# ECG_PWR_MGMT.net
KiCad netlist of a schematic drawn in Altium Designer
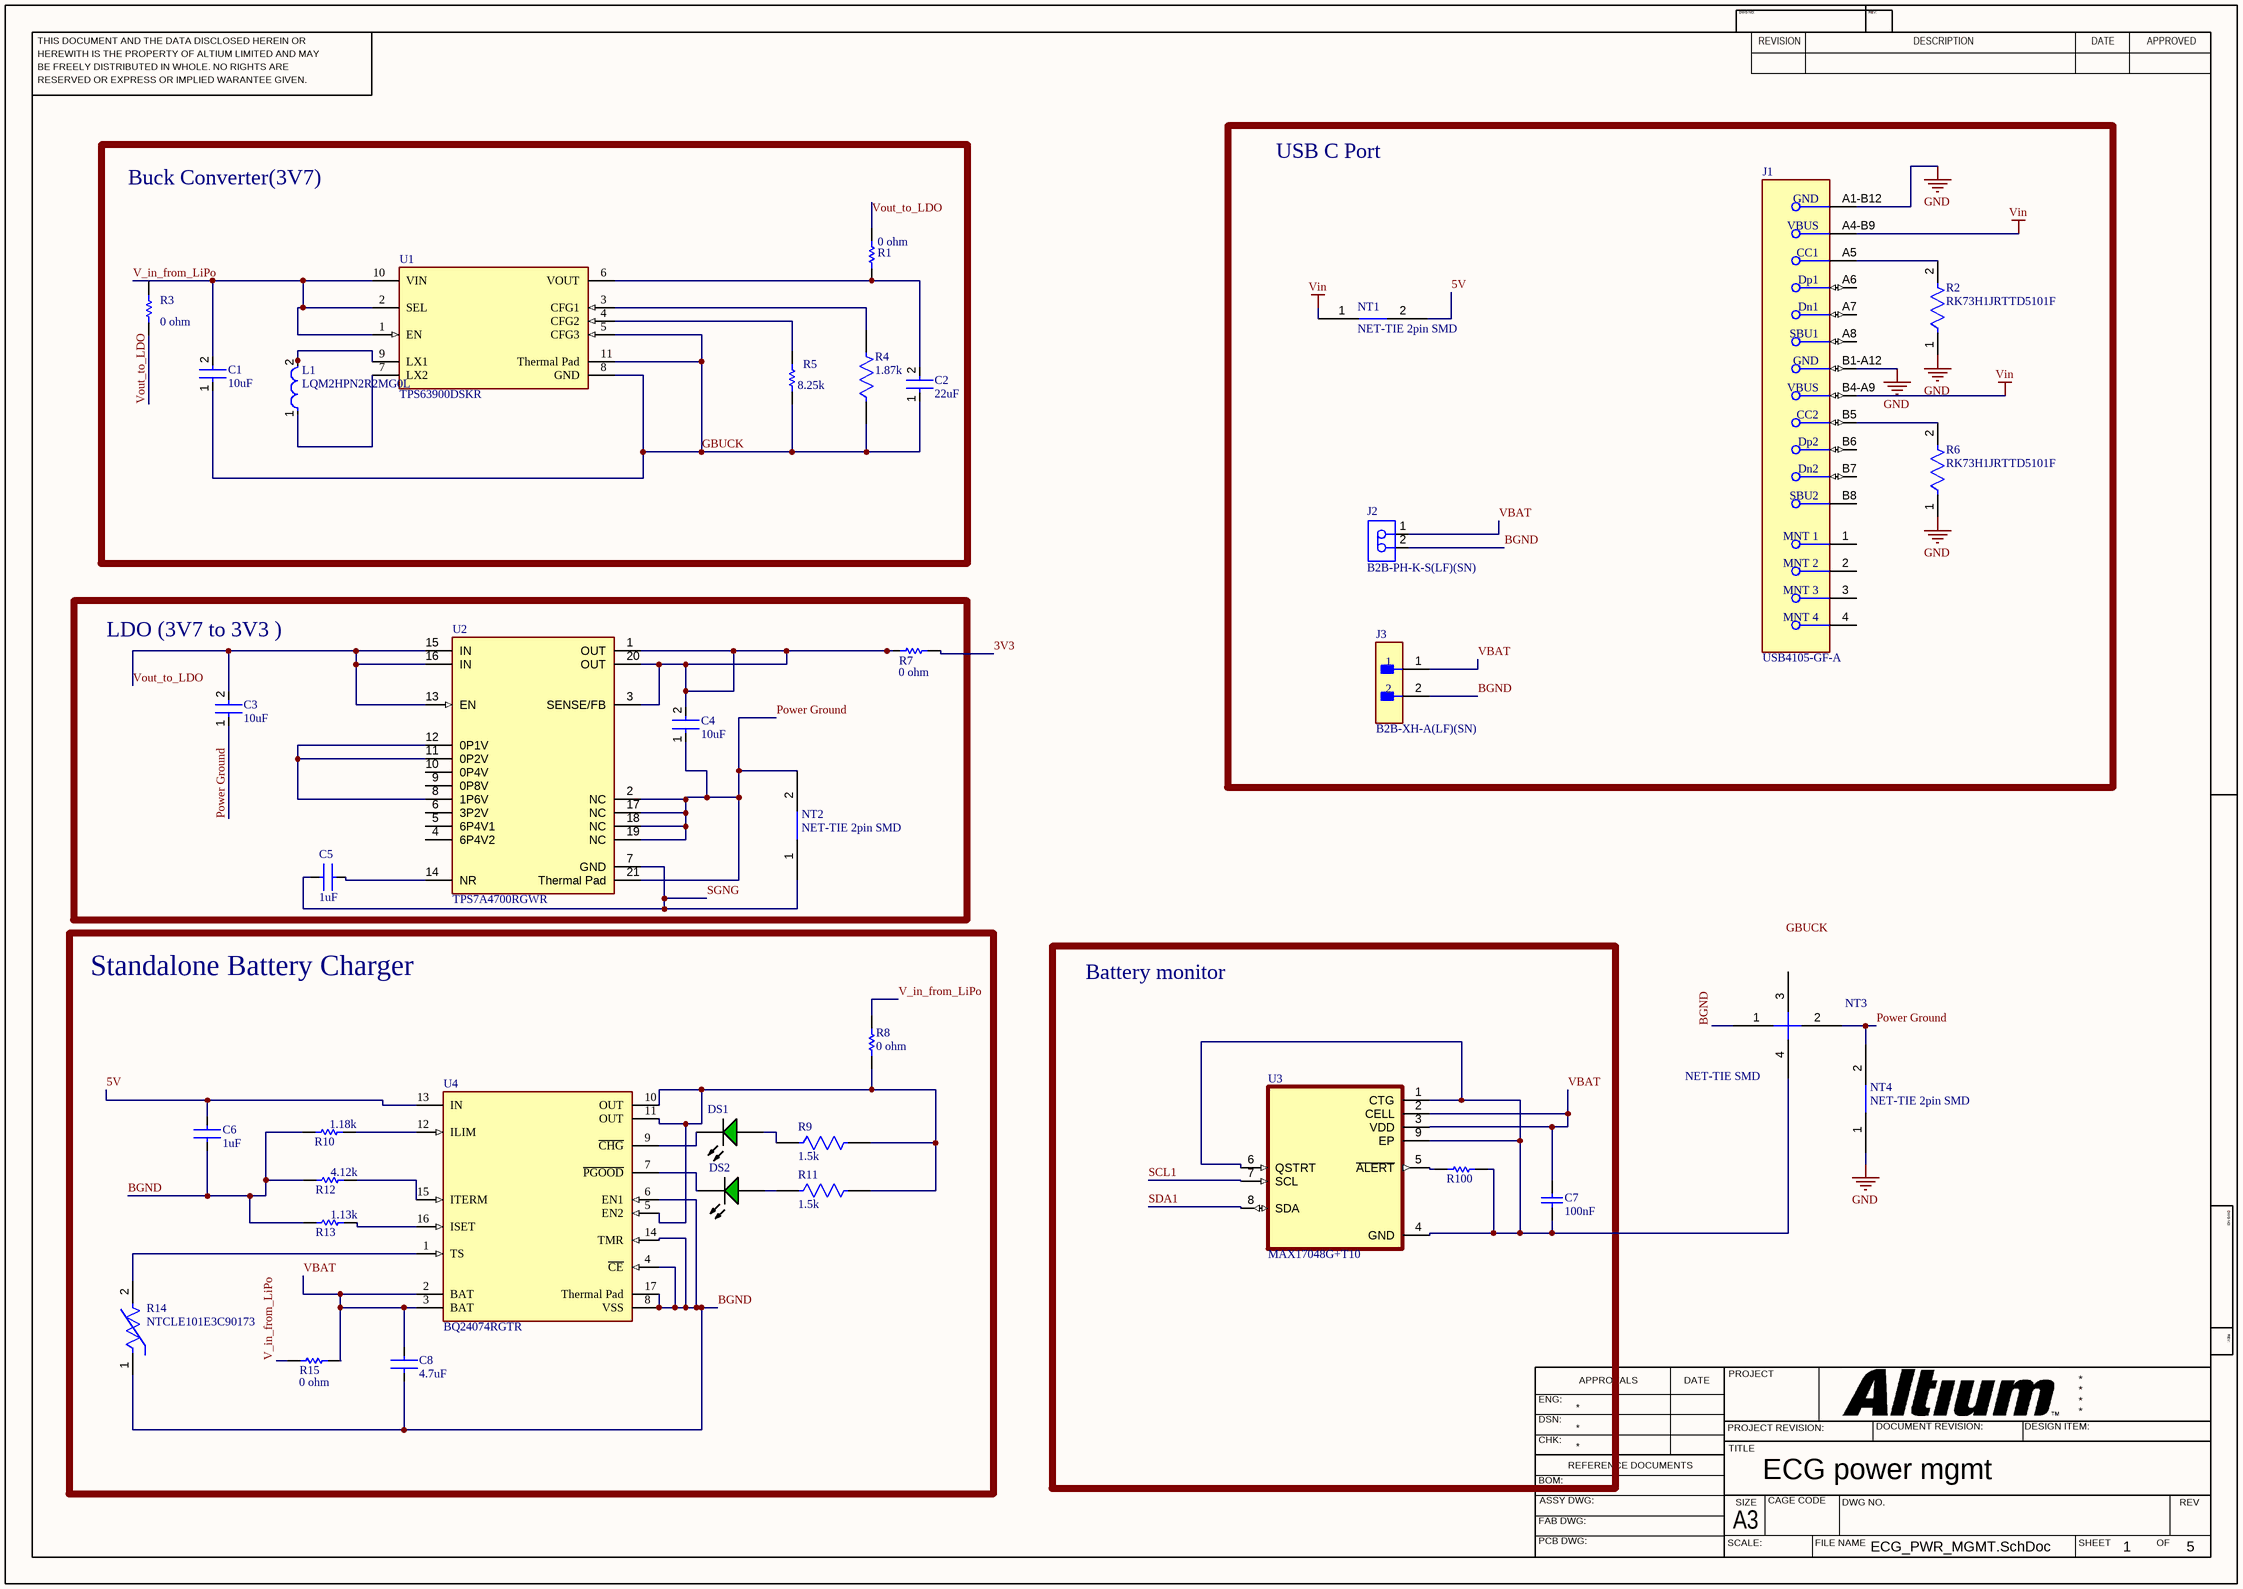
[diagram p0: ECG_PWR_MGMT.SchDoc]

(export (version "E")
  (design (tool "Eeschema 10.0.6"))
  (components
    (comp (ref "C1")
      (value "10uF")
      (footprint "CAP-0805-IPC_B")
      (description "50V 10uF X5R 卤10% 0805 Multilayer Ceramic Capacitors MLCC - SMD/SMT ROHS")
      (fields
        (field (name "MANUFACTURER") "Samsung Electro-Mechanics")
        (field (name "MANUFACTURER PART NUMBER") "CL21A106KBYQNNE")
      )
      (libsource (lib "ecg_device_components") (part "10uF CAP 0805 10V"))
    )
    (comp (ref "C2")
      (value "22uF")
      (footprint "CAP-0805-IPC_B")
      (description "10V 22uF X5R 卤10% 0805 Multilayer Ceramic Capacitors MLCC - SMD/SMT ROHS")
      (fields
        (field (name "MANUFACTURER") "Samsung Electro-Mechanics")
        (field (name "MANUFACTURER PART NUMBER") "CL21A226KPCLRNC")
      )
      (libsource (lib "ecg_device_components") (part "22uF CAP-0805-IPC-B_2"))
    )
    (comp (ref "C3")
      (value "10uF")
      (footprint "CAP-0805-IPC_B")
      (description "50V 10uF X5R 卤10% 0805 Multilayer Ceramic Capacitors MLCC - SMD/SMT ROHS")
      (fields
        (field (name "MANUFACTURER") "Samsung Electro-Mechanics")
        (field (name "MANUFACTURER PART NUMBER") "CL21A106KBYQNNE")
      )
      (libsource (lib "ecg_device_components") (part "10uF CAP 0805 10V"))
    )
    (comp (ref "C4")
      (value "10uF")
      (footprint "CAP-0805-IPC_B")
      (description "50V 10uF X5R 卤10% 0805 Multilayer Ceramic Capacitors MLCC - SMD/SMT ROHS")
      (fields
        (field (name "MANUFACTURER") "Samsung Electro-Mechanics")
        (field (name "MANUFACTURER PART NUMBER") "CL21A106KBYQNNE")
      )
      (libsource (lib "ecg_device_components") (part "10uF CAP 0805 10V"))
    )
    (comp (ref "C5")
      (value "1uF")
      (footprint "CAP-0805-IPC_B")
      (libsource (lib "ecg_device_components") (part "1uF CAP-0805-IPC-B_1"))
    )
    (comp (ref "C6")
      (value "1uF")
      (footprint "CAP-0805-IPC_B")
      (libsource (lib "ecg_device_components") (part "1uF CAP-0805-IPC-B_1"))
    )
    (comp (ref "C7")
      (value "100nF")
      (footprint "CAP-0603-IPC_B")
      (fields
        (field (name "MANUFACTURER") "AVX Interconnect / Elco")
        (field (name "PART NUMBER") "0603ZC103MAT2A")
      )
      (libsource (lib "ecg_device_components") (part "CAP-0603-IPC-B"))
    )
    (comp (ref "C8")
      (value "4.7uF")
      (footprint "CAP-0805-IPC_B")
      (libsource (lib "ecg_device_components") (part "4.7uF CAP-0805-IPC-B_1"))
    )
    (comp (ref "DS1")
      (value "LTL-1CHG")
      (footprint "LTST-LTL-1CHG-2")
      (description "LED Uni-Color Green, 100 mW, 30 mA, -55 to 100 degC, 2-Pin THD, RoHS, Bulk")
      (fields (field (name "POWER") "100mW") (field (name "MANUFACTURER") "Lite-On"))
      (libsource (lib "Dissanayakadmdp 23") (part "LED-GREEN-AK-2"))
    )
    (comp (ref "DS2")
      (value "LTL-1CHG")
      (footprint "LTST-LTL-1CHG-2")
      (description "LED Uni-Color Green, 100 mW, 30 mA, -55 to 100 degC, 2-Pin THD, RoHS, Bulk")
      (fields (field (name "POWER") "100mW") (field (name "MANUFACTURER") "Lite-On"))
      (libsource (lib "Dissanayakadmdp 23") (part "LED-GREEN-AK-2"))
    )
    (comp (ref "J1")
      (value "USB4105-GF-A")
      (footprint "FP-USB4105-GF-A-MFG")
      (description "CONN RCPT USB2.0 TYPEC 5A")
      (fields
        (field (name "MANUFACTURER") "GCT")
        (field (name "OCTOPART") "https://octopart.com/usb4105-gf-a-gct-106627878")
      )
      (libsource (lib "Altium Content Vault") (part "e7c17a616881a82b79941196b4bec10"))
    )
    (comp (ref "J2")
      (value "B2B-PH-K-S(LF)(SN)")
      (footprint "JST-B2B-PH-K-S_V")
      (fields (field (name "MANUFACTURER") "JST"))
      (libsource (lib "Altium Content Vault") (part "CN-2P-F-QF2"))
    )
    (comp (ref "J3")
      (value "B2B-XH-A(LF)(SN)")
      (footprint "FP-B2B-XH-A_LF_SN-MFG")
      (description "CONN HEADER VERT 2POS 2.5MM")
      (libsource (lib "Altium Content Vault") (part "3bc925449376181038e59eaffc5286c"))
    )
    (comp (ref "L1")
      (value "LQM2HPN2R2MG0L")
      (footprint "FP-LQM2HPN_G0-IPC_C")
      (description "Multilayer Type Inductor for Power Lines, 1008 (2520), 2.2μH, 20%, 0.1Ω, 1.3A")
      (fields (field (name "TOLERANCE") "20%"))
      (libsource (lib "Altium Content Vault") (part "725321dda6339637d4d059423bc1c3c"))
    )
    (comp (ref "NT1")
      (value "NET-TIE 2pin SMD")
      (footprint "NET TIE SMD 2 pin")
      (libsource (lib "ecg_device_components") (part "NET-TIE 2pin SMD"))
    )
    (comp (ref "NT2")
      (value "NET-TIE 2pin SMD")
      (footprint "NET TIE SMD 2 pin")
      (libsource (lib "ecg_device_components") (part "NET-TIE 2pin SMD"))
    )
    (comp (ref "NT3")
      (value "NET-TIE SMD")
      (footprint "NET TIE SMD")
      (libsource (lib "ecg_device_components") (part "NET-TIE SMD"))
    )
    (comp (ref "NT4")
      (value "NET-TIE 2pin SMD")
      (footprint "NET TIE SMD 2 pin")
      (libsource (lib "ecg_device_components") (part "NET-TIE 2pin SMD"))
    )
    (comp (ref "R1")
      (value "0 ohm")
      (footprint "RES-0603-IPC_B")
      (fields (field (name "TOLERANCE") "0.5%"))
      (libsource (lib "ecg_device_components") (part "RES-0603-IPC-B"))
    )
    (comp (ref "R2")
      (value "RK73H1JRTTD5101F")
      (footprint "FP-RK73H1J-IPC_C")
      (description "5.1kΩ ±1% 0.1W Chip Resistor 0603 Flat Chip (Anti-Sulfuration) AEC-Q200 Qualified")
      (fields (field (name "TOLERANCE") "1%"))
      (libsource (lib "Altium Content Vault") (part "1029c3af85768c4190bb7ad29bc67b5"))
    )
    (comp (ref "R3")
      (value "0 ohm")
      (footprint "RES-0603-IPC_B")
      (fields (field (name "TOLERANCE") "0.5%"))
      (libsource (lib "ecg_device_components") (part "RES-0603-IPC-B"))
    )
    (comp (ref "R4")
      (value "1.87k")
      (footprint "RES 0805 Medium")
      (description "200mW Thick Film Resistors ±50ppm/℃ ±0.1% 1.87kΩ 0805 Chip Resistor - Surface Mount ROHS")
      (fields
        (field (name "MANUFACTURER") "Panasonic")
        (field (name "MANUFACTURER PART NUMBER") "ERJPB6B1871V")
      )
      (libsource (lib "ecg_device_components") (part "1.87k RES-0805-IPC_B_1"))
    )
    (comp (ref "R5")
      (value "8.25k")
      (footprint "RES-0603-IPC_B")
      (description "Res Thin Film 0603 8.25K Ohm 0.1% 0.1W(1/10W) ±25ppm/C Pad SMD T/R Automotive AEC-Q200")
      (fields (field (name "TOLERANCE") "0.5%") (field (name "MANUFACTURER") "Panasonic"))
      (libsource (lib "ecg_device_components") (part "8.25k RES-0603-IPC-B_1"))
    )
    (comp (ref "R6")
      (value "RK73H1JRTTD5101F")
      (footprint "FP-RK73H1J-IPC_C")
      (description "5.1kΩ ±1% 0.1W Chip Resistor 0603 Flat Chip (Anti-Sulfuration) AEC-Q200 Qualified")
      (fields (field (name "TOLERANCE") "1%"))
      (libsource (lib "Altium Content Vault") (part "1029c3af85768c4190bb7ad29bc67b5"))
    )
    (comp (ref "R7")
      (value "0 ohm")
      (footprint "RES-0603-IPC_B")
      (fields (field (name "TOLERANCE") "0.5%"))
      (libsource (lib "ecg_device_components") (part "RES-0603-IPC-B"))
    )
    (comp (ref "R8")
      (value "0 ohm")
      (footprint "RES-0603-IPC_B")
      (fields (field (name "TOLERANCE") "0.5%"))
      (libsource (lib "ecg_device_components") (part "RES-0603-IPC-B"))
    )
    (comp (ref "R9")
      (value "1.5k")
      (footprint "RES 0805 Medium")
      (libsource (lib "ecg_device_components") (part "RES-0805-IPC_B"))
    )
    (comp (ref "R10")
      (value "1.18k")
      (footprint "RES-0603-IPC_B")
      (fields (field (name "TOLERANCE") "0.5%"))
      (libsource (lib "ecg_device_components") (part "1.18k RES-0603-IPC-B_3"))
    )
    (comp (ref "R11")
      (value "1.5k")
      (footprint "RES 0805 Medium")
      (libsource (lib "ecg_device_components") (part "RES-0805-IPC_B"))
    )
    (comp (ref "R12")
      (value "4.12k")
      (footprint "RES-0603-IPC_B")
      (fields (field (name "TOLERANCE") "0.5%"))
      (libsource (lib "ecg_device_components") (part "4.12k RES-0603-IPC-B_1"))
    )
    (comp (ref "R13")
      (value "1.13k")
      (footprint "RES-0603-IPC_B")
      (fields (field (name "TOLERANCE") "0.5%"))
      (libsource (lib "ecg_device_components") (part "1.13k RES-0603-IPC-B_2"))
    )
    (comp (ref "R14")
      (value "NTCLE101E3C90173")
      (footprint "FP-NTCLE101E3C90173-MFG")
      (description "THERM NTC 10KOHM 3435K RADIAL")
      (fields (field (name "TOLERANCE") "1%"))
      (libsource (lib "Altium Content Vault") (part "3b148a6ebabc5fb4d708a66c052d352"))
    )
    (comp (ref "R15")
      (value "0 ohm")
      (footprint "RES-0603-IPC_B")
      (fields (field (name "TOLERANCE") "0.5%"))
      (libsource (lib "ecg_device_components") (part "RES-0603-IPC-B"))
    )
    (comp (ref "R100")
      (value "1k RES-0603-IPC-B_1")
      (footprint "RES-0603-IPC_B")
      (fields (field (name "TOLERANCE") "0.5%"))
      (libsource (lib "ecg_device_components") (part "1k RES-0603-IPC-B_1"))
    )
    (comp (ref "U1")
      (value "TPS63900DSKR")
      (footprint "FP-DSK0010A-IPC_C")
      (description "1.8-V TO 5.5-V, 75-NA IQ BUCK-BO")
      (libsource (lib "Altium Content Vault") (part "087cbe63ebfe39a16d3bf11a348b5dd"))
    )
    (comp (ref "U2")
      (value "TPS7A4700RGWR")
      (footprint "FP-RGW0020A-MFG")
      (description "IC REG LINEAR POS ADJ 1A 20VQFN")
      (fields
        (field (name "OCTOPART") "https://octopart.com/tps7a4700rgwr-texas+instruments-21221956")
        (field (name "MANUFACTURER") "Texas Instruments")
      )
      (libsource (lib "Altium Content Vault") (part "8e99b082ac9f85253ef2256b190b767"))
    )
    (comp (ref "U3")
      (value "MAX17048G+T10")
      (footprint "max17048g+t10")
      (description "3ÂµA 1-Cell/2-Cell Fuel Gauge with ModelGauge")
      (fields (field (name "MF") "Analog Devices"))
      (libsource (lib "ecg_device_components") (part "MAX17048G+T10"))
    )
    (comp (ref "U4")
      (value "BQ24074RGTR")
      (footprint "FP-RGT0016C-IPC_B")
      (description "IC LI-ION CHARGE MGMT 16-QFN")
      (libsource (lib "Altium Content Vault") (part "bc0294d1c007ba64400ebcffad863a1"))
    )
  )
  (nets
    (net (code "1") (name "/3V3") (class "Default")
      (node (ref "R7") (pin "2") (pinfunction "2_2") (pintype "passive"))
    )
    (net (code "2") (name "/5V") (class "Default")
      (node (ref "C6") (pin "2") (pinfunction "2_2") (pintype "passive"))
      (node (ref "NT1") (pin "2") (pinfunction "1_2") (pintype "passive"))
      (node (ref "U4") (pin "13") (pinfunction "IN_13") (pintype "power_in"))
    )
    (net (code "3") (name "/BGND") (class "Default")
      (node (ref "C6") (pin "1") (pinfunction "1_1") (pintype "passive"))
      (node (ref "C8") (pin "1") (pinfunction "1_1") (pintype "passive"))
      (node (ref "J2") (pin "2") (pinfunction "2_2") (pintype "passive"))
      (node (ref "J3") (pin "2") (pinfunction "2_2") (pintype "passive"))
      (node (ref "NT3") (pin "1") (pinfunction "0_1") (pintype "passive"))
      (node (ref "R10") (pin "1") (pinfunction "1_1") (pintype "passive"))
      (node (ref "R12") (pin "1") (pinfunction "1_1") (pintype "passive"))
      (node (ref "R13") (pin "1") (pinfunction "1_1") (pintype "passive"))
      (node (ref "R14") (pin "1") (pinfunction "1_1") (pintype "passive"))
      (node (ref "U4") (pin "14") (pinfunction "TMR_14") (pintype "input"))
      (node (ref "U4") (pin "17") (pinfunction "Thermal_Pad_17") (pintype "power_in"))
      (node (ref "U4") (pin "4") (pinfunction "~{CE}_4") (pintype "input"))
      (node (ref "U4") (pin "6") (pinfunction "EN1_6") (pintype "input"))
      (node (ref "U4") (pin "8") (pinfunction "VSS_8") (pintype "power_in"))
    )
    (net (code "4") (name "/GBUCK") (class "Default")
      (node (ref "C1") (pin "1") (pinfunction "1_1") (pintype "passive"))
      (node (ref "C2") (pin "1") (pinfunction "1_1") (pintype "passive"))
      (node (ref "R4") (pin "1") (pinfunction "1_1") (pintype "passive"))
      (node (ref "R5") (pin "1") (pinfunction "1_1") (pintype "passive"))
      (node (ref "U1") (pin "11") (pinfunction "Thermal_Pad_11") (pintype "power_in"))
      (node (ref "U1") (pin "5") (pinfunction "CFG3_5") (pintype "input"))
      (node (ref "U1") (pin "8") (pinfunction "GND_8") (pintype "power_in"))
    )
    (net (code "5") (name "/Power Ground") (class "Default")
      (node (ref "C3") (pin "1") (pinfunction "1_1") (pintype "passive"))
      (node (ref "C4") (pin "1") (pinfunction "1_1") (pintype "passive"))
      (node (ref "NT2") (pin "2") (pinfunction "1_2") (pintype "passive"))
      (node (ref "NT3") (pin "2") (pinfunction "1_2") (pintype "passive"))
      (node (ref "NT4") (pin "2") (pinfunction "1_2") (pintype "passive"))
      (node (ref "U2") (pin "17") (pinfunction "NC_17") (pintype "passive"))
      (node (ref "U2") (pin "18") (pinfunction "NC_18") (pintype "passive"))
      (node (ref "U2") (pin "19") (pinfunction "NC_19") (pintype "passive"))
      (node (ref "U2") (pin "2") (pinfunction "NC_2") (pintype "passive"))
      (node (ref "U2") (pin "21") (pinfunction "Thermal_Pad_21") (pintype "power_in"))
    )
    (net (code "6") (name "/SCL1") (class "Default")
      (node (ref "U3") (pin "7") (pinfunction "SCL_7") (pintype "input"))
    )
    (net (code "7") (name "/SDA1") (class "Default")
      (node (ref "U3") (pin "8") (pinfunction "SDA_8") (pintype "bidirectional"))
    )
    (net (code "8") (name "/SGNG") (class "Default")
      (node (ref "C5") (pin "1") (pinfunction "1_1") (pintype "passive"))
      (node (ref "NT2") (pin "1") (pinfunction "0_1") (pintype "passive"))
      (node (ref "U2") (pin "7") (pinfunction "GND_7") (pintype "power_in"))
    )
    (net (code "9") (name "/VBAT") (class "Default")
      (node (ref "C7") (pin "2") (pinfunction "2_2") (pintype "passive"))
      (node (ref "C8") (pin "2") (pinfunction "2_2") (pintype "passive"))
      (node (ref "J2") (pin "1") (pinfunction "1_1") (pintype "passive"))
      (node (ref "J3") (pin "1") (pinfunction "1_1") (pintype "passive"))
      (node (ref "R15") (pin "2") (pinfunction "2_2") (pintype "passive"))
      (node (ref "U3") (pin "2") (pinfunction "CELL_2") (pintype "power_in"))
      (node (ref "U3") (pin "3") (pinfunction "VDD_3") (pintype "power_in"))
      (node (ref "U4") (pin "2") (pinfunction "BAT_2") (pintype "power_in"))
      (node (ref "U4") (pin "3") (pinfunction "BAT_3") (pintype "power_in"))
    )
    (net (code "10") (name "/V_in_from_LiPo") (class "Default")
      (node (ref "C1") (pin "2") (pinfunction "2_2") (pintype "passive"))
      (node (ref "R15") (pin "1") (pinfunction "1_1") (pintype "passive"))
      (node (ref "R8") (pin "2") (pinfunction "2_2") (pintype "passive"))
      (node (ref "U1") (pin "1") (pinfunction "EN_1") (pintype "input"))
      (node (ref "U1") (pin "10") (pinfunction "VIN_10") (pintype "power_in"))
      (node (ref "U1") (pin "2") (pinfunction "SEL_2") (pintype "passive"))
    )
    (net (code "11") (name "/Vout_to_LDO") (class "Default")
      (node (ref "C3") (pin "2") (pinfunction "2_2") (pintype "passive"))
      (node (ref "R1") (pin "2") (pinfunction "2_2") (pintype "passive"))
      (node (ref "R3") (pin "1") (pinfunction "1_1") (pintype "passive"))
      (node (ref "U2") (pin "13") (pinfunction "EN_13") (pintype "input"))
      (node (ref "U2") (pin "15") (pinfunction "IN_15") (pintype "power_in"))
      (node (ref "U2") (pin "16") (pinfunction "IN_16") (pintype "power_in"))
    )
    (net (code "12") (name "GND") (class "Default")
      (node (ref "J1") (pin "A1-B12") (pinfunction "GND_A1-B12") (pintype "power_in"))
      (node (ref "J1") (pin "B1-A12") (pinfunction "GND_B1-A12") (pintype "bidirectional"))
      (node (ref "NT4") (pin "1") (pinfunction "0_1") (pintype "passive"))
      (node (ref "R2") (pin "1") (pinfunction "1_1") (pintype "passive"))
      (node (ref "R6") (pin "1") (pinfunction "1_1") (pintype "passive"))
    )
    (net (code "13") (name "Net-(DS1-A)") (class "Default")
      (node (ref "DS1") (pin "1") (pinfunction "A_1") (pintype "passive"))
      (node (ref "R9") (pin "1") (pinfunction "1_1") (pintype "passive"))
    )
    (net (code "14") (name "Net-(DS1-K)") (class "Default")
      (node (ref "DS1") (pin "2") (pinfunction "K_2") (pintype "passive"))
      (node (ref "U4") (pin "9") (pinfunction "~{CHG}_9") (pintype "tri_state"))
    )
    (net (code "15") (name "Net-(DS2-A)") (class "Default")
      (node (ref "DS2") (pin "1") (pinfunction "A_1") (pintype "passive"))
      (node (ref "R11") (pin "1") (pinfunction "1_1") (pintype "passive"))
    )
    (net (code "16") (name "Net-(DS2-K)") (class "Default")
      (node (ref "DS2") (pin "2") (pinfunction "K_2") (pintype "passive"))
      (node (ref "U4") (pin "7") (pinfunction "~{PGOOD}_7") (pintype "tri_state"))
    )
    (net (code "17") (name "Net-(J1-CC1)") (class "Default")
      (node (ref "J1") (pin "A5") (pinfunction "CC1_A5") (pintype "power_in"))
      (node (ref "R2") (pin "2") (pinfunction "2_2") (pintype "passive"))
    )
    (net (code "18") (name "Net-(J1-CC2)") (class "Default")
      (node (ref "J1") (pin "B5") (pinfunction "CC2_B5") (pintype "bidirectional"))
      (node (ref "R6") (pin "2") (pinfunction "2_2") (pintype "passive"))
    )
    (net (code "19") (name "Net-(U1-CFG1)") (class "Default")
      (node (ref "R4") (pin "2") (pinfunction "2_2") (pintype "passive"))
      (node (ref "U1") (pin "3") (pinfunction "CFG1_3") (pintype "input"))
    )
    (net (code "20") (name "Net-(U1-CFG2)") (class "Default")
      (node (ref "R5") (pin "2") (pinfunction "2_2") (pintype "passive"))
      (node (ref "U1") (pin "4") (pinfunction "CFG2_4") (pintype "input"))
    )
    (net (code "21") (name "Net-(U1-LX1)") (class "Default")
      (node (ref "L1") (pin "2") (pinfunction "2_2") (pintype "passive"))
      (node (ref "U1") (pin "9") (pinfunction "LX1_9") (pintype "passive"))
    )
    (net (code "22") (name "Net-(U1-LX2)") (class "Default")
      (node (ref "L1") (pin "1") (pinfunction "1_1") (pintype "passive"))
      (node (ref "U1") (pin "7") (pinfunction "LX2_7") (pintype "passive"))
    )
    (net (code "23") (name "Net-(U1-VOUT)") (class "Default")
      (node (ref "C2") (pin "2") (pinfunction "2_2") (pintype "passive"))
      (node (ref "R1") (pin "1") (pinfunction "1_1") (pintype "passive"))
      (node (ref "U1") (pin "6") (pinfunction "VOUT_6") (pintype "passive"))
    )
    (net (code "24") (name "Net-(U2-0P1V)") (class "Default")
      (node (ref "U2") (pin "11") (pinfunction "0P2V_11") (pintype "passive"))
      (node (ref "U2") (pin "12") (pinfunction "0P1V_12") (pintype "passive"))
      (node (ref "U2") (pin "8") (pinfunction "1P6V_8") (pintype "passive"))
    )
    (net (code "25") (name "Net-(U2-NR)") (class "Default")
      (node (ref "C5") (pin "2") (pinfunction "2_2") (pintype "passive"))
      (node (ref "U2") (pin "14") (pinfunction "NR_14") (pintype "passive"))
    )
    (net (code "26") (name "Net-(U2-SENSE{slash}FB)") (class "Default")
      (node (ref "C4") (pin "2") (pinfunction "2_2") (pintype "passive"))
      (node (ref "R7") (pin "1") (pinfunction "1_1") (pintype "passive"))
      (node (ref "U2") (pin "1") (pinfunction "OUT_1") (pintype "power_in"))
      (node (ref "U2") (pin "20") (pinfunction "OUT_20") (pintype "power_in"))
      (node (ref "U2") (pin "3") (pinfunction "SENSE/FB_3") (pintype "passive"))
    )
    (net (code "27") (name "Net-(U3-CTG)") (class "Default")
      (node (ref "C7") (pin "1") (pinfunction "1_1") (pintype "passive"))
      (node (ref "NT3") (pin "4") (pinfunction "4_4") (pintype "passive"))
      (node (ref "R100") (pin "2") (pinfunction "2_2") (pintype "passive"))
      (node (ref "U3") (pin "1") (pinfunction "CTG_1") (pintype "power_in"))
      (node (ref "U3") (pin "4") (pinfunction "GND_4") (pintype "power_in"))
      (node (ref "U3") (pin "6") (pinfunction "QSTRT_6") (pintype "input"))
      (node (ref "U3") (pin "9") (pinfunction "EP_9") (pintype "power_in"))
    )
    (net (code "28") (name "Net-(U3-~{ALERT})") (class "Default")
      (node (ref "R100") (pin "1") (pinfunction "1_1") (pintype "passive"))
      (node (ref "U3") (pin "5") (pinfunction "~{ALERT}_5") (pintype "output"))
    )
    (net (code "29") (name "Net-(U4-EN2)") (class "Default")
      (node (ref "R11") (pin "2") (pinfunction "2_2") (pintype "passive"))
      (node (ref "R8") (pin "1") (pinfunction "1_1") (pintype "passive"))
      (node (ref "R9") (pin "2") (pinfunction "2_2") (pintype "passive"))
      (node (ref "U4") (pin "10") (pinfunction "OUT_10") (pintype "power_in"))
      (node (ref "U4") (pin "11") (pinfunction "OUT_11") (pintype "power_in"))
      (node (ref "U4") (pin "5") (pinfunction "EN2_5") (pintype "input"))
    )
    (net (code "30") (name "Net-(U4-ILIM)") (class "Default")
      (node (ref "R10") (pin "2") (pinfunction "2_2") (pintype "passive"))
      (node (ref "U4") (pin "12") (pinfunction "ILIM_12") (pintype "input"))
    )
    (net (code "31") (name "Net-(U4-ISET)") (class "Default")
      (node (ref "R13") (pin "2") (pinfunction "2_2") (pintype "passive"))
      (node (ref "U4") (pin "16") (pinfunction "ISET_16") (pintype "input"))
    )
    (net (code "32") (name "Net-(U4-ITERM)") (class "Default")
      (node (ref "R12") (pin "2") (pinfunction "2_2") (pintype "passive"))
      (node (ref "U4") (pin "15") (pinfunction "ITERM_15") (pintype "input"))
    )
    (net (code "33") (name "Net-(U4-TS)") (class "Default")
      (node (ref "R14") (pin "2") (pinfunction "2_2") (pintype "passive"))
      (node (ref "U4") (pin "1") (pinfunction "TS_1") (pintype "input"))
    )
    (net (code "34") (name "Vin") (class "Default")
      (node (ref "J1") (pin "A4-B9") (pinfunction "VBUS_A4-B9") (pintype "power_in"))
      (node (ref "J1") (pin "B4-A9") (pinfunction "VBUS_B4-A9") (pintype "bidirectional"))
      (node (ref "NT1") (pin "1") (pinfunction "0_1") (pintype "passive"))
    )
    (net (code "35") (name "unconnected-(J1-Dn1-PadA7)") (class "Default")
      (node (ref "J1") (pin "A7") (pinfunction "Dn1_A7") (pintype "bidirectional"))
    )
    (net (code "36") (name "unconnected-(J1-Dn2-PadB7)") (class "Default")
      (node (ref "J1") (pin "B7") (pinfunction "Dn2_B7") (pintype "bidirectional"))
    )
    (net (code "37") (name "unconnected-(J1-Dp1-PadA6)") (class "Default")
      (node (ref "J1") (pin "A6") (pinfunction "Dp1_A6") (pintype "bidirectional"))
    )
    (net (code "38") (name "unconnected-(J1-Dp2-PadB6)") (class "Default")
      (node (ref "J1") (pin "B6") (pinfunction "Dp2_B6") (pintype "bidirectional"))
    )
    (net (code "39") (name "unconnected-(J1-MNT_1-Pad1)") (class "Default")
      (node (ref "J1") (pin "1") (pinfunction "MNT_1_1") (pintype "power_in"))
    )
    (net (code "40") (name "unconnected-(J1-MNT_2-Pad2)") (class "Default")
      (node (ref "J1") (pin "2") (pinfunction "MNT_2_2") (pintype "power_in"))
    )
    (net (code "41") (name "unconnected-(J1-MNT_3-Pad3)") (class "Default")
      (node (ref "J1") (pin "3") (pinfunction "MNT_3_3") (pintype "power_in"))
    )
    (net (code "42") (name "unconnected-(J1-MNT_4-Pad4)") (class "Default")
      (node (ref "J1") (pin "4") (pinfunction "MNT_4_4") (pintype "power_in"))
    )
    (net (code "43") (name "unconnected-(J1-SBU1-PadA8)") (class "Default")
      (node (ref "J1") (pin "A8") (pinfunction "SBU1_A8") (pintype "bidirectional"))
    )
    (net (code "44") (name "unconnected-(J1-SBU2-PadB8)") (class "Default")
      (node (ref "J1") (pin "B8") (pinfunction "SBU2_B8") (pintype "power_in"))
    )
    (net (code "45") (name "unconnected-(NT3-Pad3)") (class "Default")
      (node (ref "NT3") (pin "3") (pinfunction "3_3") (pintype "passive"))
    )
    (net (code "46") (name "unconnected-(R3-Pad2)") (class "Default")
      (node (ref "R3") (pin "2") (pinfunction "2_2") (pintype "passive"))
    )
    (net (code "47") (name "unconnected-(U2-0P4V-Pad10)") (class "Default")
      (node (ref "U2") (pin "10") (pinfunction "0P4V_10") (pintype "passive"))
    )
    (net (code "48") (name "unconnected-(U2-0P8V-Pad9)") (class "Default")
      (node (ref "U2") (pin "9") (pinfunction "0P8V_9") (pintype "passive"))
    )
    (net (code "49") (name "unconnected-(U2-3P2V-Pad6)") (class "Default")
      (node (ref "U2") (pin "6") (pinfunction "3P2V_6") (pintype "passive"))
    )
    (net (code "50") (name "unconnected-(U2-6P4V1-Pad5)") (class "Default")
      (node (ref "U2") (pin "5") (pinfunction "6P4V1_5") (pintype "passive"))
    )
    (net (code "51") (name "unconnected-(U2-6P4V2-Pad4)") (class "Default")
      (node (ref "U2") (pin "4") (pinfunction "6P4V2_4") (pintype "passive"))
    )
  )
)
